# BLDC.net
KiCad netlist of a schematic drawn in Altium Designer
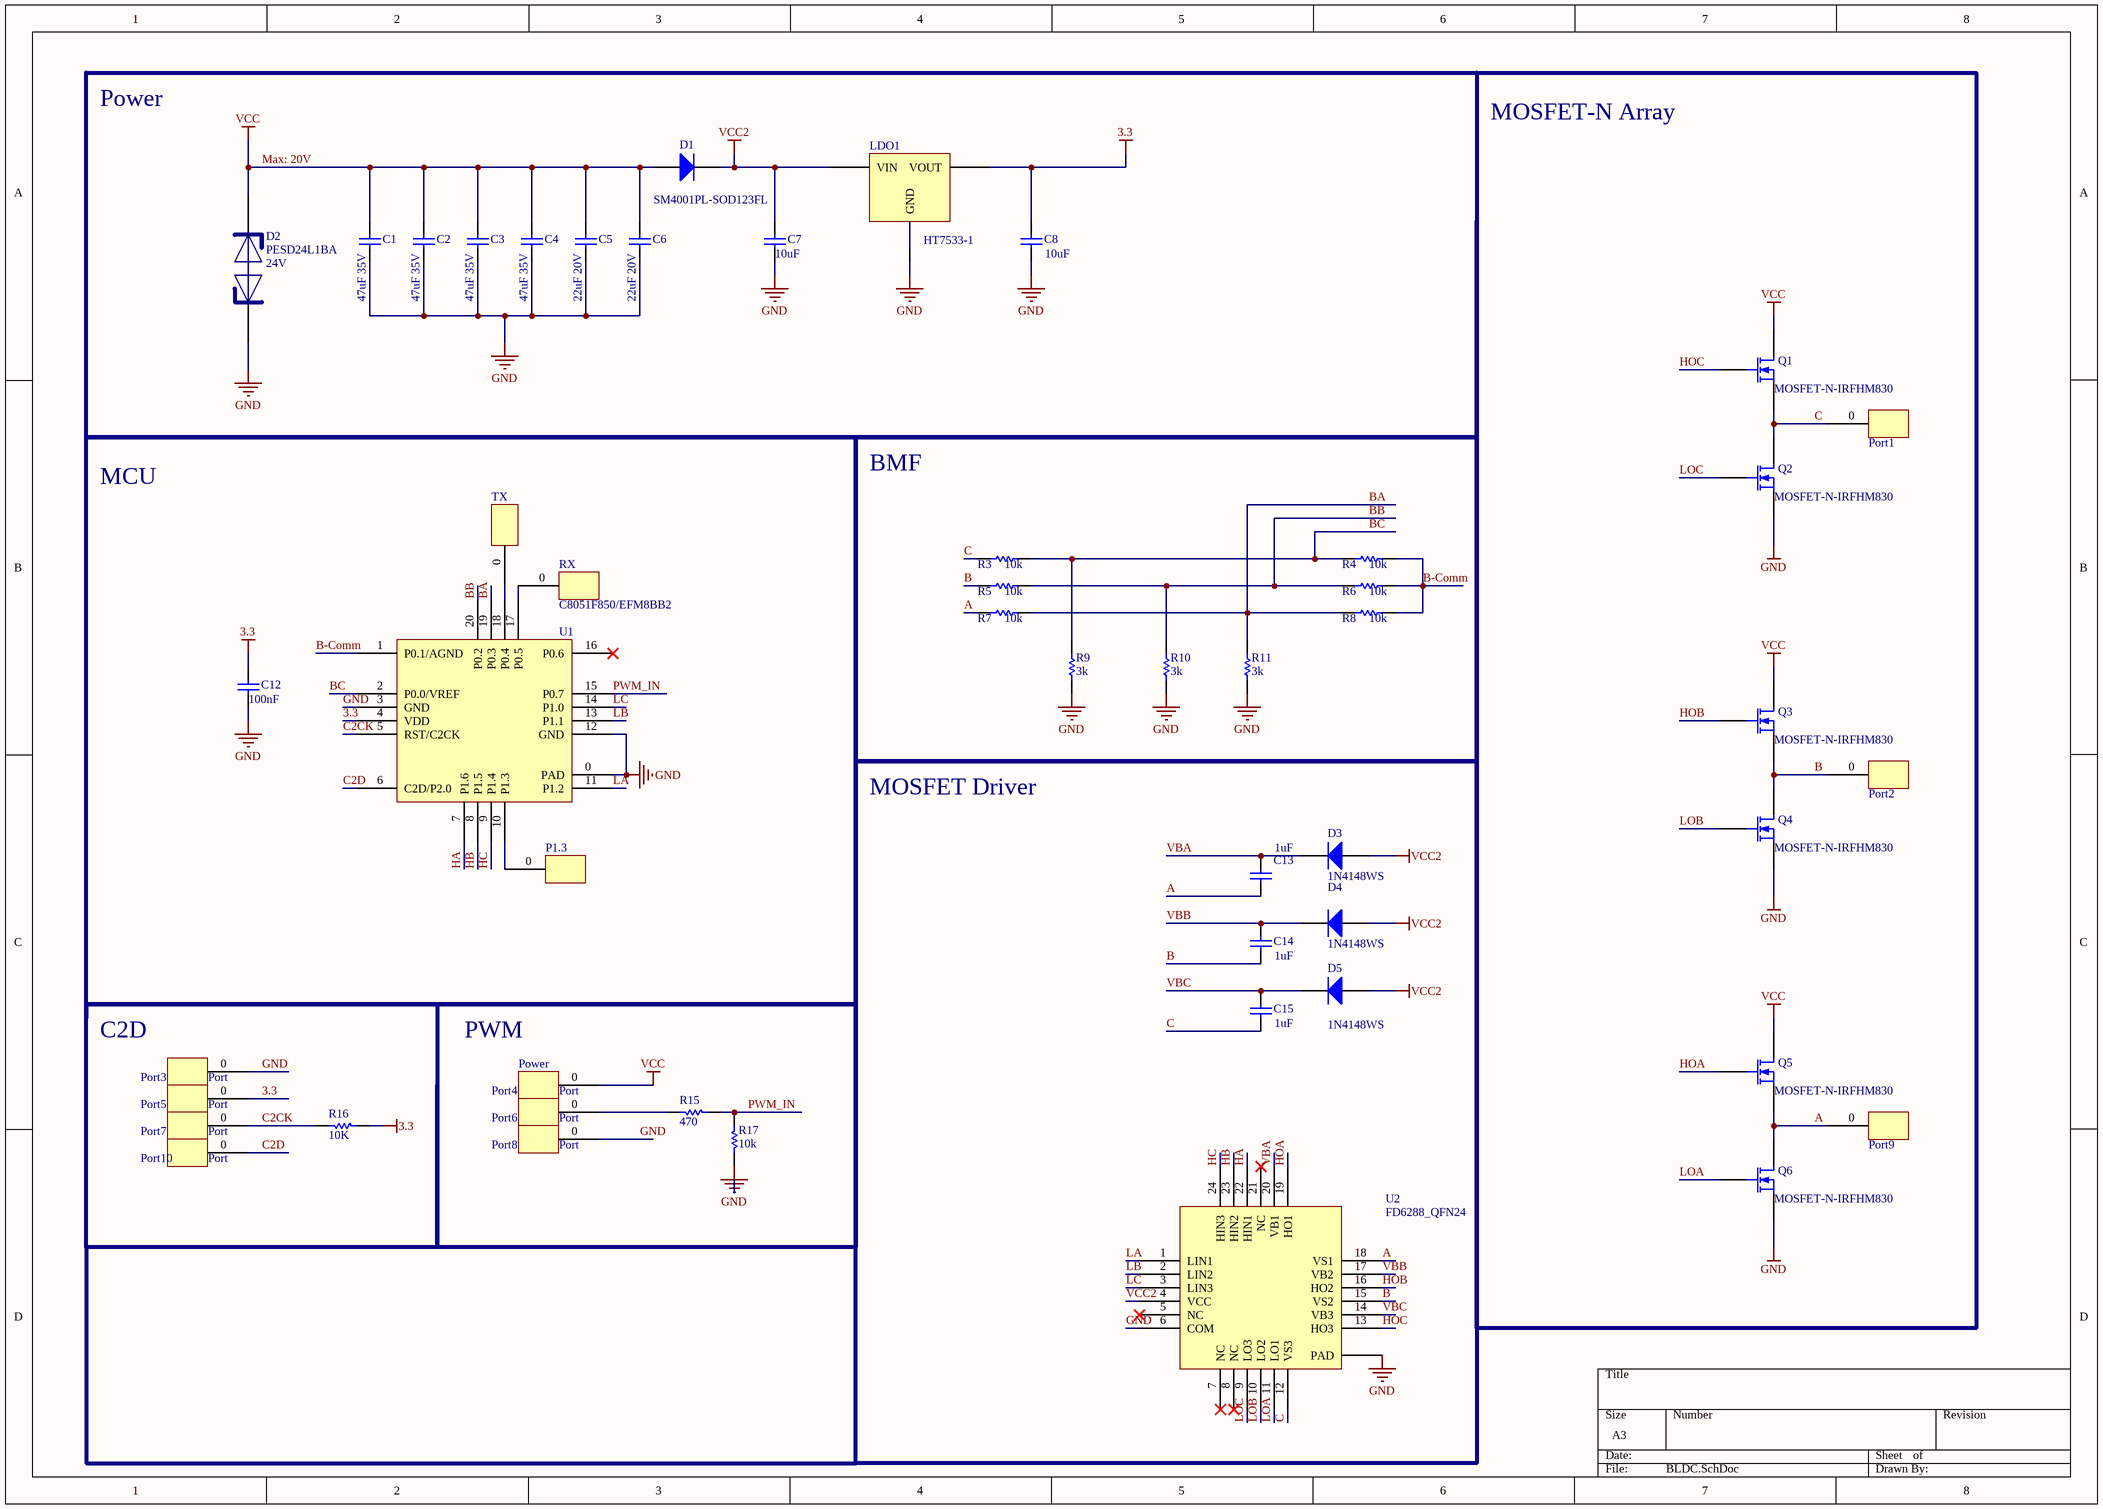
[diagram p0: BLDC.SchDoc]

(export (version "E")
  (design (tool "Eeschema 10.0.6"))
  (components
    (comp (ref "C1")
      (value "47uF 35V")
      (footprint "1206_HIGH")
      (description "Capacitor")
      (fields (field (name "Comment") "Cap") (field (name "PUBLISHER") "Altium Limited"))
      (libsource (lib "Miscellaneous Devices") (part "Cap"))
    )
    (comp (ref "C2")
      (value "47uF 35V")
      (footprint "1206_HIGH")
      (description "Capacitor")
      (fields (field (name "Comment") "Cap") (field (name "PUBLISHER") "Altium Limited"))
      (libsource (lib "Miscellaneous Devices") (part "Cap"))
    )
    (comp (ref "C3")
      (value "47uF 35V")
      (footprint "1206_HIGH")
      (description "Capacitor")
      (fields (field (name "Comment") "Cap") (field (name "PUBLISHER") "Altium Limited"))
      (libsource (lib "Miscellaneous Devices") (part "Cap"))
    )
    (comp (ref "C4")
      (value "47uF 35V")
      (footprint "1206_HIGH")
      (description "Capacitor")
      (fields (field (name "Comment") "Cap") (field (name "PUBLISHER") "Altium Limited"))
      (libsource (lib "Miscellaneous Devices") (part "Cap"))
    )
    (comp (ref "C5")
      (value "22uF 20V")
      (footprint "1206_HIGH")
      (description "Capacitor")
      (fields (field (name "Comment") "Cap") (field (name "PUBLISHER") "Altium Limited"))
      (libsource (lib "Miscellaneous Devices") (part "Cap"))
    )
    (comp (ref "C6")
      (value "22uF 20V")
      (footprint "1206_HIGH")
      (description "Capacitor")
      (fields (field (name "Comment") "Cap") (field (name "PUBLISHER") "Altium Limited"))
      (libsource (lib "Miscellaneous Devices") (part "Cap"))
    )
    (comp (ref "C7")
      (value "10uF")
      (footprint "0603_HIGH")
      (description "Capacitor")
      (fields (field (name "Comment") "Cap") (field (name "PUBLISHER") "Altium Limited"))
      (libsource (lib "Miscellaneous Devices") (part "Cap"))
    )
    (comp (ref "C8")
      (value "10uF")
      (footprint "0603_HIGH")
      (description "Capacitor")
      (fields (field (name "Comment") "Cap") (field (name "PUBLISHER") "Altium Limited"))
      (libsource (lib "Miscellaneous Devices") (part "Cap"))
    )
    (comp (ref "C12")
      (value "100nF")
      (footprint "0402_High")
      (description "Capacitor")
      (fields (field (name "Comment") "Cap") (field (name "PUBLISHER") "Altium Limited"))
      (libsource (lib "Miscellaneous Devices") (part "Cap"))
    )
    (comp (ref "C13")
      (value "1uF")
      (footprint "0603_HIGH")
      (description "Capacitor")
      (fields (field (name "Comment") "Cap") (field (name "PUBLISHER") "Altium Limited"))
      (libsource (lib "Miscellaneous Devices") (part "Cap"))
    )
    (comp (ref "C14")
      (value "1uF")
      (footprint "0603_HIGH")
      (description "Capacitor")
      (fields (field (name "Comment") "Cap") (field (name "PUBLISHER") "Altium Limited"))
      (libsource (lib "Miscellaneous Devices") (part "Cap"))
    )
    (comp (ref "C15")
      (value "1uF")
      (footprint "0603_HIGH")
      (description "Capacitor")
      (fields (field (name "Comment") "Cap") (field (name "PUBLISHER") "Altium Limited"))
      (libsource (lib "Miscellaneous Devices") (part "Cap"))
    )
    (comp (ref "D1")
      (value "SM4001PL-SOD123FL")
      (footprint "SOD123")
      (description "Default Diode")
      (fields (field (name "PUBLISHER") "Altium Limited"))
      (libsource (lib "Miscellaneous Devices") (part "Diode"))
    )
    (comp (ref "D2")
      (value "PESD24L1BA")
      (footprint "SODFL250X110-2N")
      (fields (field (name "ALTIUM_VALUE") "24V"))
      (libsource (lib "SCH") (part "PESD24L1BA"))
    )
    (comp (ref "D3")
      (value "1N4148WS")
      (footprint "LC-SOD-323")
      (description "Default Diode")
      (fields (field (name "PUBLISHER") "Altium Limited"))
      (libsource (lib "Miscellaneous Devices") (part "Diode"))
    )
    (comp (ref "D4")
      (value "1N4148WS")
      (footprint "LC-SOD-323")
      (description "Default Diode")
      (fields (field (name "PUBLISHER") "Altium Limited"))
      (libsource (lib "Miscellaneous Devices") (part "Diode"))
    )
    (comp (ref "D5")
      (value "1N4148WS")
      (footprint "LC-SOD-323")
      (description "Default Diode")
      (fields (field (name "PUBLISHER") "Altium Limited"))
      (libsource (lib "Miscellaneous Devices") (part "Diode"))
    )
    (comp (ref "LDO1")
      (value "HT7533-1")
      (footprint "SOT89-150P348X160-3N")
      (libsource (lib "SCH") (part "LDO"))
    )
    (comp (ref "P1.3") (value "Port") (footprint "DEBUG_POINT") (libsource (lib "SCH") (part "Port")))
    (comp (ref "Port1") (value "Port") (footprint "MOTOR_POINT") (libsource (lib "") (part "Port_2")))
    (comp (ref "Port2") (value "Port") (footprint "MOTOR_POINT") (libsource (lib "SCH") (part "Port")))
    (comp (ref "Port3") (value "Port") (footprint "DEBUG_POINT") (libsource (lib "") (part "Port_1")))
    (comp (ref "Port4") (value "Port") (footprint "POWER_POINT") (libsource (lib "") (part "Port_1")))
    (comp (ref "Port5") (value "Port") (footprint "DEBUG_POINT") (libsource (lib "") (part "Port_1")))
    (comp (ref "Port6") (value "Port") (footprint "MOTOR_POINT") (libsource (lib "") (part "Port_1")))
    (comp (ref "Port7") (value "Port") (footprint "DEBUG_POINT") (libsource (lib "") (part "Port_1")))
    (comp (ref "Port8") (value "Port") (footprint "POWER_POINT") (libsource (lib "") (part "Port_1")))
    (comp (ref "Port9") (value "Port") (footprint "MOTOR_POINT") (libsource (lib "SCH") (part "Port")))
    (comp (ref "Port10") (value "Port") (footprint "DEBUG_POINT") (libsource (lib "") (part "Port_1")))
    (comp (ref "Q1")
      (value "MOSFET-N-IRFHM830")
      (footprint "PQFN3X3")
      (description "N-Channel MOSFET")
      (fields (field (name "PUBLISHER") "Altium Limited"))
      (libsource (lib "Miscellaneous Devices") (part "MOSFET-N"))
    )
    (comp (ref "Q2")
      (value "MOSFET-N-IRFHM830")
      (footprint "PQFN3X3")
      (description "N-Channel MOSFET")
      (fields (field (name "PUBLISHER") "Altium Limited"))
      (libsource (lib "Miscellaneous Devices") (part "MOSFET-N"))
    )
    (comp (ref "Q3")
      (value "MOSFET-N-IRFHM830")
      (footprint "PQFN3X3")
      (description "N-Channel MOSFET")
      (fields (field (name "PUBLISHER") "Altium Limited"))
      (libsource (lib "Miscellaneous Devices") (part "MOSFET-N"))
    )
    (comp (ref "Q4")
      (value "MOSFET-N-IRFHM830")
      (footprint "PQFN3X3")
      (description "N-Channel MOSFET")
      (fields (field (name "PUBLISHER") "Altium Limited"))
      (libsource (lib "Miscellaneous Devices") (part "MOSFET-N"))
    )
    (comp (ref "Q5")
      (value "MOSFET-N-IRFHM830")
      (footprint "PQFN3X3")
      (description "N-Channel MOSFET")
      (fields (field (name "PUBLISHER") "Altium Limited"))
      (libsource (lib "Miscellaneous Devices") (part "MOSFET-N"))
    )
    (comp (ref "Q6")
      (value "MOSFET-N-IRFHM830")
      (footprint "PQFN3X3")
      (description "N-Channel MOSFET")
      (fields (field (name "PUBLISHER") "Altium Limited"))
      (libsource (lib "Miscellaneous Devices") (part "MOSFET-N"))
    )
    (comp (ref "R3")
      (value "10k")
      (footprint "0402_High")
      (description "Resistor")
      (fields (field (name "Comment") "Res1") (field (name "PUBLISHER") "Altium Limited"))
      (libsource (lib "Miscellaneous Devices") (part "Res1"))
    )
    (comp (ref "R4")
      (value "10k")
      (footprint "0402_High")
      (description "Resistor")
      (fields (field (name "Comment") "Res1") (field (name "PUBLISHER") "Altium Limited"))
      (libsource (lib "Miscellaneous Devices") (part "Res1"))
    )
    (comp (ref "R5")
      (value "10k")
      (footprint "0402_High")
      (description "Resistor")
      (fields (field (name "Comment") "Res1") (field (name "PUBLISHER") "Altium Limited"))
      (libsource (lib "Miscellaneous Devices") (part "Res1"))
    )
    (comp (ref "R6")
      (value "10k")
      (footprint "0402_High")
      (description "Resistor")
      (fields (field (name "Comment") "Res1") (field (name "PUBLISHER") "Altium Limited"))
      (libsource (lib "Miscellaneous Devices") (part "Res1"))
    )
    (comp (ref "R7")
      (value "10k")
      (footprint "0402_High")
      (description "Resistor")
      (fields (field (name "Comment") "Res1") (field (name "PUBLISHER") "Altium Limited"))
      (libsource (lib "Miscellaneous Devices") (part "Res1"))
    )
    (comp (ref "R8")
      (value "10k")
      (footprint "0402_High")
      (description "Resistor")
      (fields (field (name "Comment") "Res1") (field (name "PUBLISHER") "Altium Limited"))
      (libsource (lib "Miscellaneous Devices") (part "Res1"))
    )
    (comp (ref "R9")
      (value "3k")
      (footprint "0402_High")
      (description "Resistor")
      (fields (field (name "Comment") "Res1") (field (name "PUBLISHER") "Altium Limited"))
      (libsource (lib "Miscellaneous Devices") (part "Res1"))
    )
    (comp (ref "R10")
      (value "3k")
      (footprint "0402_High")
      (description "Resistor")
      (fields (field (name "Comment") "Res1") (field (name "PUBLISHER") "Altium Limited"))
      (libsource (lib "Miscellaneous Devices") (part "Res1"))
    )
    (comp (ref "R11")
      (value "3k")
      (footprint "0402_High")
      (description "Resistor")
      (fields (field (name "Comment") "Res1") (field (name "PUBLISHER") "Altium Limited"))
      (libsource (lib "Miscellaneous Devices") (part "Res1"))
    )
    (comp (ref "R15")
      (value "470")
      (footprint "0402_High")
      (description "Resistor")
      (fields (field (name "Comment") "Res1") (field (name "PUBLISHER") "Altium Limited"))
      (libsource (lib "Miscellaneous Devices") (part "Res1"))
    )
    (comp (ref "R16")
      (value "10K")
      (footprint "0402_High")
      (description "Resistor")
      (fields (field (name "Comment") "Res1") (field (name "PUBLISHER") "Altium Limited"))
      (libsource (lib "Miscellaneous Devices") (part "Res1"))
    )
    (comp (ref "R17")
      (value "10k")
      (footprint "0402_High")
      (description "Resistor")
      (fields (field (name "Comment") "Res1") (field (name "PUBLISHER") "Altium Limited"))
      (libsource (lib "Miscellaneous Devices") (part "Res1"))
    )
    (comp (ref "RX") (value "Port") (footprint "DEBUG_POINT") (libsource (lib "SCH") (part "Port")))
    (comp (ref "TX") (value "Port") (footprint "DEBUG_POINT") (libsource (lib "") (part "Port_2")))
    (comp (ref "U1")
      (value "C8051F850/EFM8BB2")
      (footprint "QFN20")
      (description "U?")
      (libsource (lib "sch") (part "C8051F850"))
    )
    (comp (ref "U2")
      (value "FD6288_QFN24")
      (footprint "QFN50P400X400X80_HS-25N")
      (libsource (lib "BLDC") (part "FD6288_QFN24"))
    )
  )
  (nets
    (net (code "1") (name "/A") (class "Default")
      (node (ref "C13") (pin "2") (pinfunction "2_2") (pintype "passive"))
      (node (ref "Port9") (pin "0") (pinfunction "port_0") (pintype "passive"))
      (node (ref "Q5") (pin "1") (pinfunction "S_1") (pintype "passive"))
      (node (ref "Q6") (pin "3") (pinfunction "D_3") (pintype "passive"))
      (node (ref "R7") (pin "2") (pinfunction "2_2") (pintype "passive"))
      (node (ref "U2") (pin "18") (pinfunction "VS1_18") (pintype "passive"))
    )
    (net (code "2") (name "/B") (class "Default")
      (node (ref "C14") (pin "2") (pinfunction "2_2") (pintype "passive"))
      (node (ref "Port2") (pin "0") (pinfunction "port_0") (pintype "passive"))
      (node (ref "Q3") (pin "1") (pinfunction "S_1") (pintype "passive"))
      (node (ref "Q4") (pin "3") (pinfunction "D_3") (pintype "passive"))
      (node (ref "R5") (pin "2") (pinfunction "2_2") (pintype "passive"))
      (node (ref "U2") (pin "15") (pinfunction "VS2_15") (pintype "passive"))
    )
    (net (code "3") (name "/B-Comm") (class "Default")
      (node (ref "R4") (pin "1") (pinfunction "1_1") (pintype "passive"))
      (node (ref "R6") (pin "1") (pinfunction "1_1") (pintype "passive"))
      (node (ref "R8") (pin "1") (pinfunction "1_1") (pintype "passive"))
      (node (ref "U1") (pin "1") (pinfunction "P0.1/AGND_1") (pintype "passive"))
    )
    (net (code "4") (name "/BA") (class "Default")
      (node (ref "R11") (pin "1") (pinfunction "1_1") (pintype "passive"))
      (node (ref "R7") (pin "1") (pinfunction "1_1") (pintype "passive"))
      (node (ref "R8") (pin "2") (pinfunction "2_2") (pintype "passive"))
      (node (ref "U1") (pin "19") (pinfunction "P0.3_19") (pintype "passive"))
    )
    (net (code "5") (name "/BB") (class "Default")
      (node (ref "R10") (pin "1") (pinfunction "1_1") (pintype "passive"))
      (node (ref "R5") (pin "1") (pinfunction "1_1") (pintype "passive"))
      (node (ref "R6") (pin "2") (pinfunction "2_2") (pintype "passive"))
      (node (ref "U1") (pin "20") (pinfunction "P0.2_20") (pintype "passive"))
    )
    (net (code "6") (name "/BC") (class "Default")
      (node (ref "R3") (pin "1") (pinfunction "1_1") (pintype "passive"))
      (node (ref "R4") (pin "2") (pinfunction "2_2") (pintype "passive"))
      (node (ref "R9") (pin "1") (pinfunction "1_1") (pintype "passive"))
      (node (ref "U1") (pin "2") (pinfunction "P0.0/VREF_2") (pintype "passive"))
    )
    (net (code "7") (name "/C") (class "Default")
      (node (ref "C15") (pin "2") (pinfunction "2_2") (pintype "passive"))
      (node (ref "Port1") (pin "0") (pinfunction "port_0") (pintype "passive"))
      (node (ref "Q1") (pin "1") (pinfunction "S_1") (pintype "passive"))
      (node (ref "Q2") (pin "3") (pinfunction "D_3") (pintype "passive"))
      (node (ref "R3") (pin "2") (pinfunction "2_2") (pintype "passive"))
      (node (ref "U2") (pin "12") (pinfunction "VS3_12") (pintype "passive"))
    )
    (net (code "8") (name "/C2CK") (class "Default")
      (node (ref "Port7") (pin "0") (pinfunction "port_0") (pintype "passive"))
      (node (ref "R16") (pin "2") (pinfunction "2_2") (pintype "passive"))
      (node (ref "U1") (pin "5") (pinfunction "RST/C2CK_5") (pintype "passive"))
    )
    (net (code "9") (name "/C2D") (class "Default")
      (node (ref "Port10") (pin "0") (pinfunction "port_0") (pintype "passive"))
      (node (ref "U1") (pin "6") (pinfunction "C2D/P2.0_6") (pintype "passive"))
    )
    (net (code "10") (name "/HA") (class "Default")
      (node (ref "U1") (pin "7") (pinfunction "P1.6_7") (pintype "passive"))
      (node (ref "U2") (pin "22") (pinfunction "HIN1_22") (pintype "passive"))
    )
    (net (code "11") (name "/HB") (class "Default")
      (node (ref "U1") (pin "8") (pinfunction "P1.5_8") (pintype "passive"))
      (node (ref "U2") (pin "23") (pinfunction "HIN2_23") (pintype "passive"))
    )
    (net (code "12") (name "/HC") (class "Default")
      (node (ref "U1") (pin "9") (pinfunction "P1.4_9") (pintype "passive"))
      (node (ref "U2") (pin "24") (pinfunction "HIN3_24") (pintype "passive"))
    )
    (net (code "13") (name "/HOA") (class "Default")
      (node (ref "Q5") (pin "2") (pinfunction "G_2") (pintype "passive"))
      (node (ref "U2") (pin "19") (pinfunction "HO1_19") (pintype "passive"))
    )
    (net (code "14") (name "/HOB") (class "Default")
      (node (ref "Q3") (pin "2") (pinfunction "G_2") (pintype "passive"))
      (node (ref "U2") (pin "16") (pinfunction "HO2_16") (pintype "passive"))
    )
    (net (code "15") (name "/HOC") (class "Default")
      (node (ref "Q1") (pin "2") (pinfunction "G_2") (pintype "passive"))
      (node (ref "U2") (pin "13") (pinfunction "HO3_13") (pintype "passive"))
    )
    (net (code "16") (name "/LA") (class "Default")
      (node (ref "U1") (pin "11") (pinfunction "P1.2_11") (pintype "passive"))
      (node (ref "U2") (pin "1") (pinfunction "LIN1_1") (pintype "passive"))
    )
    (net (code "17") (name "/LB") (class "Default")
      (node (ref "U1") (pin "13") (pinfunction "P1.1_13") (pintype "passive"))
      (node (ref "U2") (pin "2") (pinfunction "LIN2_2") (pintype "passive"))
    )
    (net (code "18") (name "/LC") (class "Default")
      (node (ref "U1") (pin "14") (pinfunction "P1.0_14") (pintype "passive"))
      (node (ref "U2") (pin "3") (pinfunction "LIN3_3") (pintype "passive"))
    )
    (net (code "19") (name "/LOA") (class "Default")
      (node (ref "Q6") (pin "2") (pinfunction "G_2") (pintype "passive"))
      (node (ref "U2") (pin "11") (pinfunction "LO1_11") (pintype "passive"))
    )
    (net (code "20") (name "/LOB") (class "Default")
      (node (ref "Q4") (pin "2") (pinfunction "G_2") (pintype "passive"))
      (node (ref "U2") (pin "10") (pinfunction "LO2_10") (pintype "passive"))
    )
    (net (code "21") (name "/LOC") (class "Default")
      (node (ref "Q2") (pin "2") (pinfunction "G_2") (pintype "passive"))
      (node (ref "U2") (pin "9") (pinfunction "LO3_9") (pintype "passive"))
    )
    (net (code "22") (name "/PWM_IN") (class "Default")
      (node (ref "R15") (pin "2") (pinfunction "2_2") (pintype "passive"))
      (node (ref "R17") (pin "2") (pinfunction "2_2") (pintype "passive"))
      (node (ref "U1") (pin "15") (pinfunction "P0.7_15") (pintype "passive"))
    )
    (net (code "23") (name "/VBA") (class "Default")
      (node (ref "C13") (pin "1") (pinfunction "1_1") (pintype "passive"))
      (node (ref "D3") (pin "2") (pinfunction "K_2") (pintype "passive"))
      (node (ref "U2") (pin "20") (pinfunction "VB1_20") (pintype "passive"))
    )
    (net (code "24") (name "/VBB") (class "Default")
      (node (ref "C14") (pin "1") (pinfunction "1_1") (pintype "passive"))
      (node (ref "D4") (pin "2") (pinfunction "K_2") (pintype "passive"))
      (node (ref "U2") (pin "17") (pinfunction "VB2_17") (pintype "passive"))
    )
    (net (code "25") (name "/VBC") (class "Default")
      (node (ref "C15") (pin "1") (pinfunction "1_1") (pintype "passive"))
      (node (ref "D5") (pin "2") (pinfunction "K_2") (pintype "passive"))
      (node (ref "U2") (pin "14") (pinfunction "VB3_14") (pintype "passive"))
    )
    (net (code "26") (name "3.3") (class "Default")
      (node (ref "C12") (pin "1") (pinfunction "1_1") (pintype "passive"))
      (node (ref "C8") (pin "1") (pinfunction "1_1") (pintype "passive"))
      (node (ref "LDO1") (pin "3") (pinfunction "VOUT_3") (pintype "passive"))
      (node (ref "Port5") (pin "0") (pinfunction "port_0") (pintype "passive"))
      (node (ref "R16") (pin "1") (pinfunction "1_1") (pintype "passive"))
      (node (ref "U1") (pin "4") (pinfunction "VDD_4") (pintype "passive"))
    )
    (net (code "27") (name "GND") (class "Default")
      (node (ref "C1") (pin "2") (pinfunction "2_2") (pintype "passive"))
      (node (ref "C12") (pin "2") (pinfunction "2_2") (pintype "passive"))
      (node (ref "C2") (pin "2") (pinfunction "2_2") (pintype "passive"))
      (node (ref "C3") (pin "2") (pinfunction "2_2") (pintype "passive"))
      (node (ref "C4") (pin "2") (pinfunction "2_2") (pintype "passive"))
      (node (ref "C5") (pin "2") (pinfunction "2_2") (pintype "passive"))
      (node (ref "C6") (pin "2") (pinfunction "2_2") (pintype "passive"))
      (node (ref "C7") (pin "2") (pinfunction "2_2") (pintype "passive"))
      (node (ref "C8") (pin "2") (pinfunction "2_2") (pintype "passive"))
      (node (ref "D2") (pin "2") (pinfunction "2_2") (pintype "passive"))
      (node (ref "LDO1") (pin "1") (pinfunction "GND_1") (pintype "passive"))
      (node (ref "Port3") (pin "0") (pinfunction "port_0") (pintype "passive"))
      (node (ref "Port8") (pin "0") (pinfunction "port_0") (pintype "passive"))
      (node (ref "Q2") (pin "1") (pinfunction "S_1") (pintype "passive"))
      (node (ref "Q4") (pin "1") (pinfunction "S_1") (pintype "passive"))
      (node (ref "Q6") (pin "1") (pinfunction "S_1") (pintype "passive"))
      (node (ref "R10") (pin "2") (pinfunction "2_2") (pintype "passive"))
      (node (ref "R11") (pin "2") (pinfunction "2_2") (pintype "passive"))
      (node (ref "R17") (pin "1") (pinfunction "1_1") (pintype "passive"))
      (node (ref "R9") (pin "2") (pinfunction "2_2") (pintype "passive"))
      (node (ref "U1") (pin "0") (pinfunction "PAD_0") (pintype "passive"))
      (node (ref "U1") (pin "12") (pinfunction "GND_12") (pintype "passive"))
      (node (ref "U1") (pin "3") (pinfunction "GND_3") (pintype "passive"))
      (node (ref "U2") (pin "0") (pinfunction "PAD_0") (pintype "passive"))
      (node (ref "U2") (pin "6") (pinfunction "COM_6") (pintype "passive"))
    )
    (net (code "28") (name "Net-(P1.3-port)") (class "Default")
      (node (ref "P1.3") (pin "0") (pinfunction "port_0") (pintype "passive"))
      (node (ref "U1") (pin "10") (pinfunction "P1.3_10") (pintype "passive"))
    )
    (net (code "29") (name "Net-(Port6-port)") (class "Default")
      (node (ref "Port6") (pin "0") (pinfunction "port_0") (pintype "passive"))
      (node (ref "R15") (pin "1") (pinfunction "1_1") (pintype "passive"))
    )
    (net (code "30") (name "Net-(RX-port)") (class "Default")
      (node (ref "RX") (pin "0") (pinfunction "port_0") (pintype "passive"))
      (node (ref "U1") (pin "17") (pinfunction "P0.5_17") (pintype "passive"))
    )
    (net (code "31") (name "Net-(TX-port)") (class "Default")
      (node (ref "TX") (pin "0") (pinfunction "port_0") (pintype "passive"))
      (node (ref "U1") (pin "18") (pinfunction "P0.4_18") (pintype "passive"))
    )
    (net (code "32") (name "VCC") (class "Default")
      (node (ref "C1") (pin "1") (pinfunction "1_1") (pintype "passive"))
      (node (ref "C2") (pin "1") (pinfunction "1_1") (pintype "passive"))
      (node (ref "C3") (pin "1") (pinfunction "1_1") (pintype "passive"))
      (node (ref "C4") (pin "1") (pinfunction "1_1") (pintype "passive"))
      (node (ref "C5") (pin "1") (pinfunction "1_1") (pintype "passive"))
      (node (ref "C6") (pin "1") (pinfunction "1_1") (pintype "passive"))
      (node (ref "D1") (pin "1") (pinfunction "A_1") (pintype "passive"))
      (node (ref "D2") (pin "1") (pinfunction "1_1") (pintype "passive"))
      (node (ref "Port4") (pin "0") (pinfunction "port_0") (pintype "passive"))
      (node (ref "Q1") (pin "3") (pinfunction "D_3") (pintype "passive"))
      (node (ref "Q3") (pin "3") (pinfunction "D_3") (pintype "passive"))
      (node (ref "Q5") (pin "3") (pinfunction "D_3") (pintype "passive"))
    )
    (net (code "33") (name "VCC2") (class "Default")
      (node (ref "C7") (pin "1") (pinfunction "1_1") (pintype "passive"))
      (node (ref "D1") (pin "2") (pinfunction "K_2") (pintype "passive"))
      (node (ref "D3") (pin "1") (pinfunction "A_1") (pintype "passive"))
      (node (ref "D4") (pin "1") (pinfunction "A_1") (pintype "passive"))
      (node (ref "D5") (pin "1") (pinfunction "A_1") (pintype "passive"))
      (node (ref "LDO1") (pin "2") (pinfunction "VIN_2") (pintype "passive"))
      (node (ref "U2") (pin "4") (pinfunction "VCC_4") (pintype "passive"))
    )
    (net (code "34") (name "unconnected-(U1-P0.6-Pad16)") (class "Default")
      (node (ref "U1") (pin "16") (pinfunction "P0.6_16") (pintype "passive+no_connect"))
    )
    (net (code "35") (name "unconnected-(U2-NC-Pad5)") (class "Default")
      (node (ref "U2") (pin "5") (pinfunction "NC_5") (pintype "passive+no_connect"))
    )
    (net (code "36") (name "unconnected-(U2-NC-Pad7)") (class "Default")
      (node (ref "U2") (pin "7") (pinfunction "NC_7") (pintype "passive+no_connect"))
    )
    (net (code "37") (name "unconnected-(U2-NC-Pad8)") (class "Default")
      (node (ref "U2") (pin "8") (pinfunction "NC_8") (pintype "passive+no_connect"))
    )
    (net (code "38") (name "unconnected-(U2-NC-Pad21)") (class "Default")
      (node (ref "U2") (pin "21") (pinfunction "NC_21") (pintype "passive+no_connect"))
    )
  )
)
